# CS1237-24-Bit-ADC.net
KiCad netlist of a schematic drawn in Altium Designer
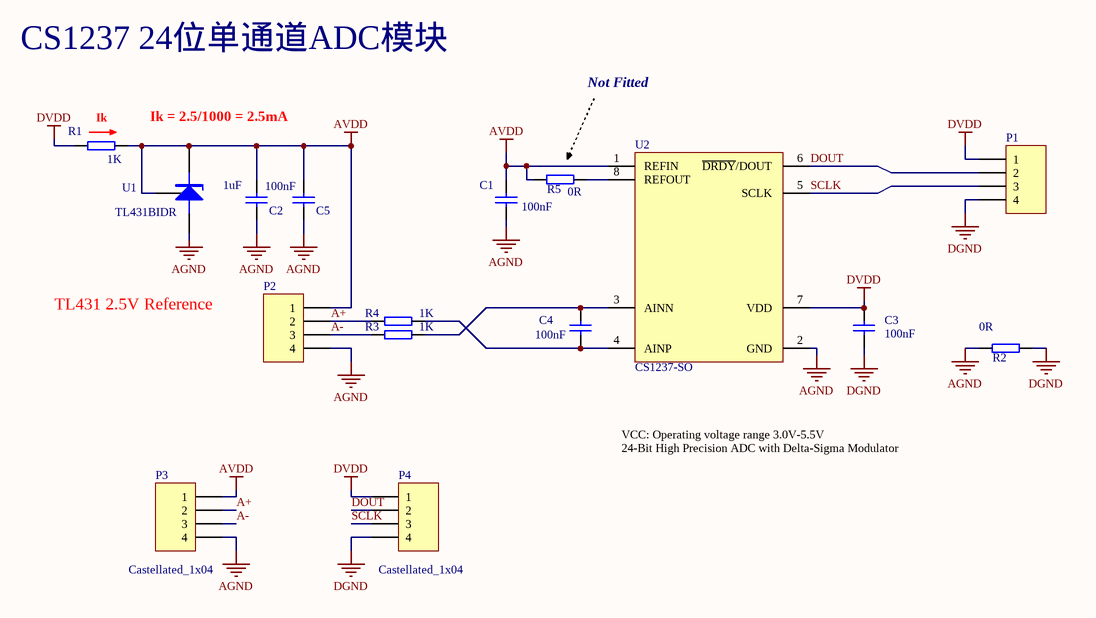
[diagram p0: CS1237-24-Bit-ADC.SchDoc]

(export (version "E")
  (design (tool "Eeschema 10.0.6"))
  (components
    (comp (ref "C1")
      (value "100nF")
      (footprint "C0603")
      (description "Capacitor, X5R, ±10%, 6.3V")
      (fields
        (field (name "PART NUMBER") "C0603-N.C.")
        (field (name "MANUFACTURER") "N.A.")
        (field (name "PUBLISHER") "Nordic Semiconductor")
      )
      (libsource (lib "adafruit") (part "Cap_0603"))
    )
    (comp (ref "C2")
      (value "1uF")
      (footprint "C0603")
      (description "Capacitor, X5R, ±10%, 6.3V")
      (fields
        (field (name "PART NUMBER") "C0603-N.C.")
        (field (name "MANUFACTURER") "N.A.")
        (field (name "PUBLISHER") "Nordic Semiconductor")
      )
      (libsource (lib "adafruit") (part "Cap_0603"))
    )
    (comp (ref "C3")
      (value "100nF")
      (footprint "C0603")
      (description "Capacitor, X5R, ±10%, 6.3V")
      (fields
        (field (name "PART NUMBER") "C0603-N.C.")
        (field (name "MANUFACTURER") "N.A.")
        (field (name "PUBLISHER") "Nordic Semiconductor")
      )
      (libsource (lib "adafruit") (part "Cap_0603"))
    )
    (comp (ref "C4")
      (value "100nF")
      (footprint "C0603")
      (description "Capacitor, X5R, ±10%, 6.3V")
      (fields
        (field (name "PART NUMBER") "C0603-N.C.")
        (field (name "MANUFACTURER") "N.A.")
        (field (name "PUBLISHER") "Nordic Semiconductor")
      )
      (libsource (lib "adafruit") (part "Cap_0603"))
    )
    (comp (ref "C5")
      (value "100nF")
      (footprint "C0603")
      (description "Capacitor, X5R, ±10%, 6.3V")
      (fields
        (field (name "PART NUMBER") "C0603-N.C.")
        (field (name "MANUFACTURER") "N.A.")
        (field (name "PUBLISHER") "Nordic Semiconductor")
      )
      (libsource (lib "adafruit") (part "Cap_0603"))
    )
    (comp (ref "P1")
      (value "~")
      (footprint "HDR1X4")
      (description "Header, 4-Pin")
      (fields (field (name "PUBLISHER") "Altium Limited"))
      (libsource (lib "Miscellaneous Connectors") (part "Header 4"))
    )
    (comp (ref "P2")
      (value "~")
      (footprint "HDR1X4")
      (description "Header, 4-Pin")
      (fields (field (name "PUBLISHER") "Altium Limited"))
      (libsource (lib "") (part "Header 4_1"))
    )
    (comp (ref "P3")
      (value "Castellated_1x04")
      (footprint "Castellated_1X04")
      (description "Header, 4-Pin")
      (fields (field (name "PUBLISHER") "Altium Limited"))
      (libsource (lib "adafruit") (part "Castellated_1x04"))
    )
    (comp (ref "P4")
      (value "Castellated_1x04")
      (footprint "Castellated_1X04")
      (description "Header, 4-Pin")
      (fields (field (name "PUBLISHER") "Altium Limited"))
      (libsource (lib "") (part "Castellated_1x04_1"))
    )
    (comp (ref "R1")
      (value "1kΩ")
      (footprint "R0805")
      (description "Resistor, ±1%, 0.200W")
      (libsource (lib "") (part "Res_0805_1"))
    )
    (comp (ref "R2")
      (value "0Ω")
      (footprint "R0805")
      (description "Resistor, ±1%, 0.200W")
      (libsource (lib "adafruit") (part "Res_0805"))
    )
    (comp (ref "R3")
      (value "1kΩ")
      (footprint "R0603")
      (description "Resistor, ±1%, 0.100W")
      (fields
        (field (name "PART NUMBER") "R0603-N.C.Ω")
        (field (name "MANUFACTURER") "N.A.")
        (field (name "PUBLISHER") "Nordic Semiconductor")
      )
      (libsource (lib "adafruit") (part "Res_0603"))
    )
    (comp (ref "R4")
      (value "1kΩ")
      (footprint "R0603")
      (description "Resistor, ±1%, 0.100W")
      (fields
        (field (name "PART NUMBER") "R0603-N.C.Ω")
        (field (name "MANUFACTURER") "N.A.")
        (field (name "PUBLISHER") "Nordic Semiconductor")
      )
      (libsource (lib "adafruit") (part "Res_0603"))
    )
    (comp (ref "R5")
      (value "0Ω")
      (footprint "R0603")
      (description "Resistor, ±1%, 0.100W")
      (fields
        (field (name "PART NUMBER") "R0603-N.C.Ω")
        (field (name "MANUFACTURER") "N.A.")
        (field (name "PUBLISHER") "Nordic Semiconductor")
      )
      (libsource (lib "adafruit") (part "Res_0603"))
    )
    (comp (ref "U1")
      (value "TL431BIDR")
      (footprint "SOIC-8E")
      (description "TL431, TL432 Precision Programmable Reference")
      (fields (field (name "MANUFACTURER") "TI(德州仪器)") (field (name "TOLERANCE") "±0.5%"))
      (libsource (lib "adafruit") (part "TL431BIDR"))
    )
    (comp (ref "U2")
      (value "CS1237-SO")
      (footprint "SOIC-8E")
      (description "CS1237 24-Bit High Precision ADC with Delta-Sigma Modulator")
      (fields (field (name "MANUFACTURER") "CHIPSEA(芯海科技)") (field (name "CONTRIBUTOR") "lcsc"))
      (libsource (lib "adafruit") (part "CS1237-SO_C7464028"))
    )
  )
  (nets
    (net (code "1") (name "/A+") (class "Default")
      (node (ref "P2") (pin "2") (pinfunction "2_2") (pintype "passive"))
      (node (ref "P3") (pin "2") (pinfunction "2_2") (pintype "passive"))
      (node (ref "R4") (pin "2") (pinfunction "2_2") (pintype "passive"))
    )
    (net (code "2") (name "/A-") (class "Default")
      (node (ref "P2") (pin "3") (pinfunction "3_3") (pintype "passive"))
      (node (ref "P3") (pin "3") (pinfunction "3_3") (pintype "passive"))
      (node (ref "R3") (pin "2") (pinfunction "2_2") (pintype "passive"))
    )
    (net (code "3") (name "/DOUT") (class "Default")
      (node (ref "P1") (pin "2") (pinfunction "2_2") (pintype "passive"))
      (node (ref "P4") (pin "2") (pinfunction "2_2") (pintype "passive"))
      (node (ref "U2") (pin "6") (pinfunction "~{DRDY}/DOUT_6") (pintype "passive"))
    )
    (net (code "4") (name "/SCLK") (class "Default")
      (node (ref "P1") (pin "3") (pinfunction "3_3") (pintype "passive"))
      (node (ref "P4") (pin "3") (pinfunction "3_3") (pintype "passive"))
      (node (ref "U2") (pin "5") (pinfunction "SCLK_5") (pintype "passive"))
    )
    (net (code "5") (name "AGND") (class "Default")
      (node (ref "C1") (pin "2") (pinfunction "2_2") (pintype "passive"))
      (node (ref "C2") (pin "1") (pinfunction "1_1") (pintype "passive"))
      (node (ref "C5") (pin "2") (pinfunction "2_2") (pintype "passive"))
      (node (ref "P2") (pin "4") (pinfunction "4_4") (pintype "passive"))
      (node (ref "P3") (pin "4") (pinfunction "4_4") (pintype "passive"))
      (node (ref "R2") (pin "2") (pinfunction "2_2") (pintype "passive"))
      (node (ref "U1") (pin "3") (pinfunction "A_3") (pintype "passive"))
      (node (ref "U2") (pin "2") (pinfunction "GND_2") (pintype "passive"))
    )
    (net (code "6") (name "AVDD") (class "Default")
      (node (ref "C1") (pin "1") (pinfunction "1_1") (pintype "passive"))
      (node (ref "C2") (pin "2") (pinfunction "2_2") (pintype "passive"))
      (node (ref "C5") (pin "1") (pinfunction "1_1") (pintype "passive"))
      (node (ref "P2") (pin "1") (pinfunction "1_1") (pintype "passive"))
      (node (ref "P3") (pin "1") (pinfunction "1_1") (pintype "passive"))
      (node (ref "R1") (pin "2") (pinfunction "2_2") (pintype "passive"))
      (node (ref "R5") (pin "2") (pinfunction "2_2") (pintype "passive"))
      (node (ref "U1") (pin "1") (pinfunction "K_1") (pintype "passive"))
      (node (ref "U1") (pin "8") (pinfunction "Ref_8") (pintype "passive"))
      (node (ref "U2") (pin "1") (pinfunction "REFIN_1") (pintype "passive"))
    )
    (net (code "7") (name "DGND") (class "Default")
      (node (ref "C3") (pin "2") (pinfunction "2_2") (pintype "passive"))
      (node (ref "P1") (pin "4") (pinfunction "4_4") (pintype "passive"))
      (node (ref "P4") (pin "4") (pinfunction "4_4") (pintype "passive"))
      (node (ref "R2") (pin "1") (pinfunction "1_1") (pintype "passive"))
    )
    (net (code "8") (name "DVDD") (class "Default")
      (node (ref "C3") (pin "1") (pinfunction "1_1") (pintype "passive"))
      (node (ref "P1") (pin "1") (pinfunction "1_1") (pintype "passive"))
      (node (ref "P4") (pin "1") (pinfunction "1_1") (pintype "passive"))
      (node (ref "R1") (pin "1") (pinfunction "1_1") (pintype "passive"))
      (node (ref "U2") (pin "7") (pinfunction "VDD_7") (pintype "passive"))
    )
    (net (code "9") (name "Net-(U2-AINN)") (class "Default")
      (node (ref "C4") (pin "1") (pinfunction "1_1") (pintype "passive"))
      (node (ref "R3") (pin "1") (pinfunction "1_1") (pintype "passive"))
      (node (ref "U2") (pin "3") (pinfunction "AINN_3") (pintype "passive"))
    )
    (net (code "10") (name "Net-(U2-AINP)") (class "Default")
      (node (ref "C4") (pin "2") (pinfunction "2_2") (pintype "passive"))
      (node (ref "R4") (pin "1") (pinfunction "1_1") (pintype "passive"))
      (node (ref "U2") (pin "4") (pinfunction "AINP_4") (pintype "passive"))
    )
    (net (code "11") (name "Net-(U2-REFOUT)") (class "Default")
      (node (ref "R5") (pin "1") (pinfunction "1_1") (pintype "passive"))
      (node (ref "U2") (pin "8") (pinfunction "REFOUT_8") (pintype "passive"))
    )
    (net (code "12") (name "unconnected-(U1-NC-Pad4)") (class "Default")
      (node (ref "U1") (pin "4") (pinfunction "NC_4") (pintype "passive"))
    )
    (net (code "13") (name "unconnected-(U1-NC-Pad5)") (class "Default")
      (node (ref "U1") (pin "5") (pinfunction "NC_5") (pintype "passive"))
    )
  )
)
